# ESP32Weatherstation.net
KiCad netlist of a schematic drawn in EAGLE
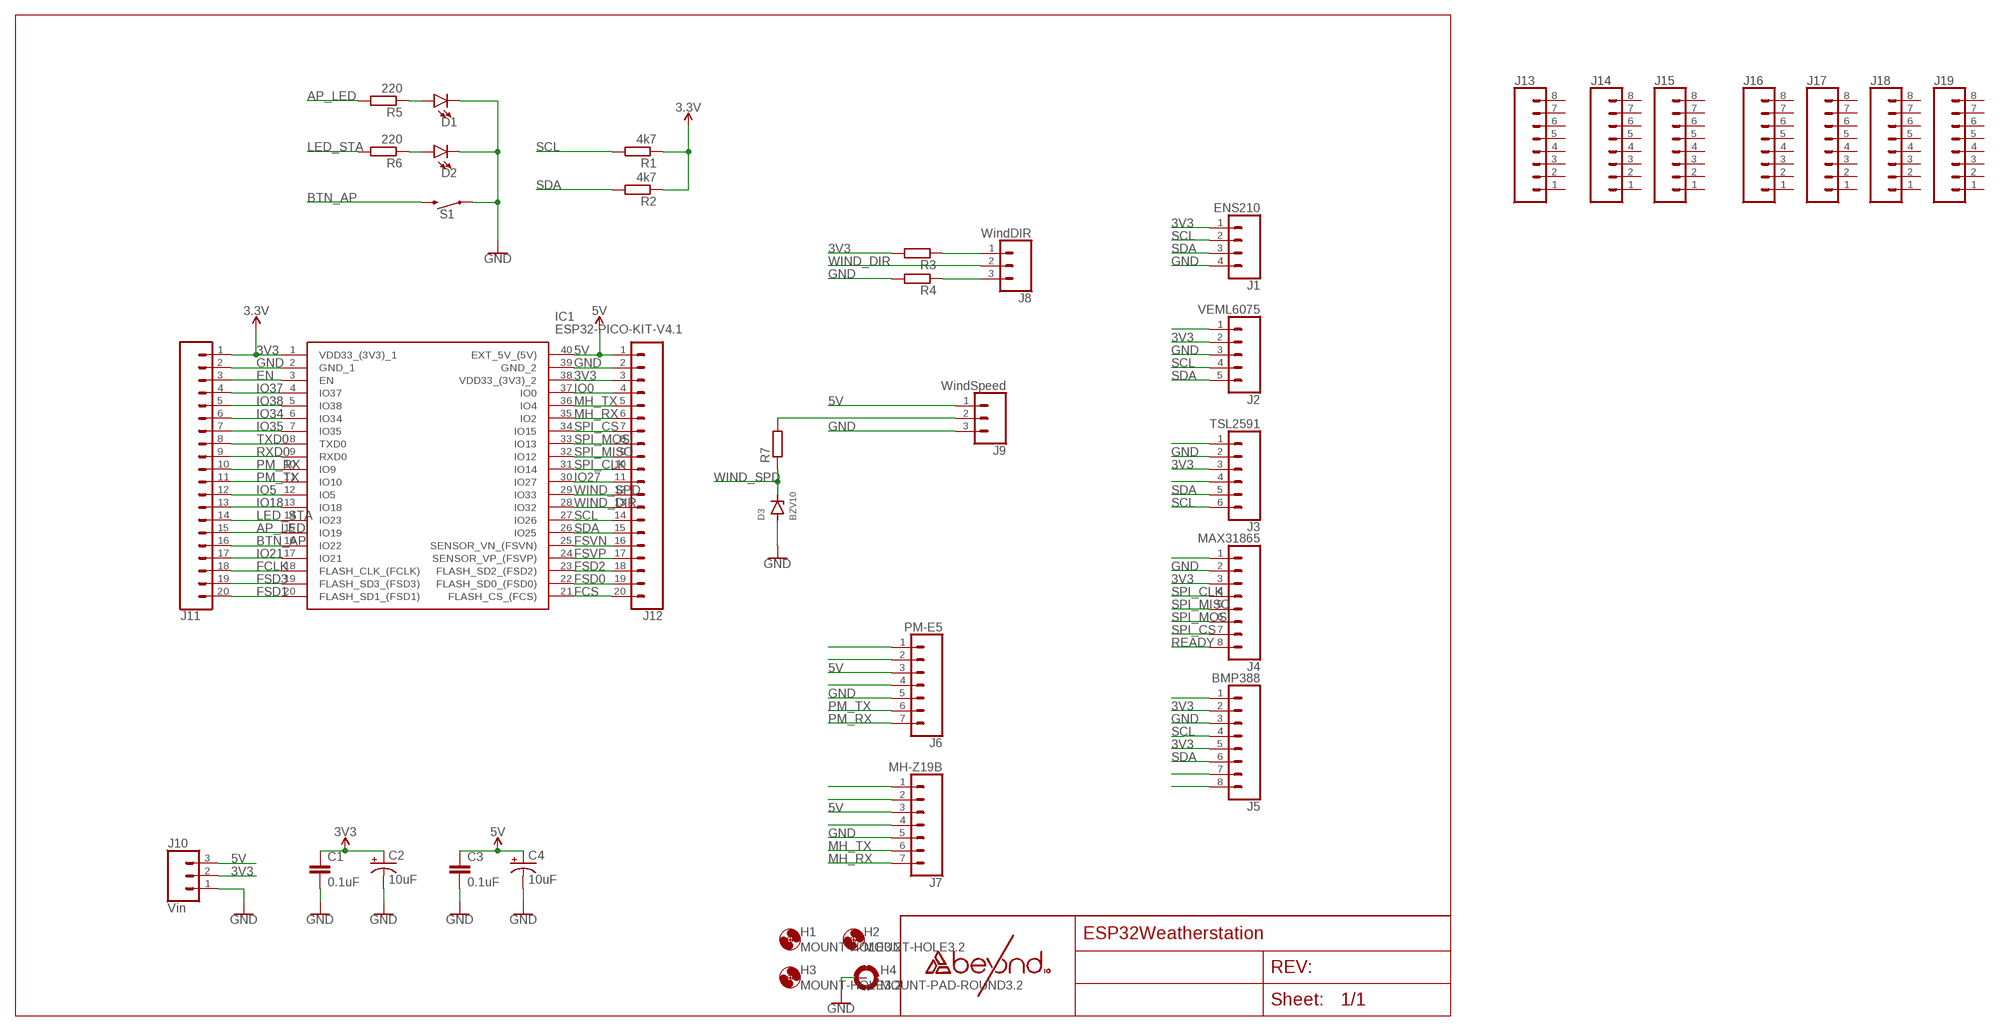
[diagram p0: schematic, sheet 1]

(export (version "E")
  (design (tool "Eeschema 10.0.6"))
  (components
    (comp (ref "C1")
      (value "0.1uF")
      (footprint "eagle-import:0603")
      (libsource (lib "eagle-import") (part "0.1UF-0603-25V-5%"))
    )
    (comp (ref "C2")
      (value "10uF")
      (footprint "eagle-import:EIA3216")
      (libsource (lib "eagle-import") (part "10UF-POLAR-EIA3216-16V-10%(TANT)"))
    )
    (comp (ref "C3")
      (value "0.1uF")
      (footprint "eagle-import:0603")
      (libsource (lib "eagle-import") (part "0.1UF-0603-25V-5%"))
    )
    (comp (ref "C4")
      (value "10uF")
      (footprint "eagle-import:EIA3216")
      (libsource (lib "eagle-import") (part "10UF-POLAR-EIA3216-16V-10%(TANT)"))
    )
    (comp (ref "D1")
      (value "LED3MM")
      (footprint "eagle-import:LED_3MM")
      (libsource (lib "eagle-import") (part "LED3MM"))
    )
    (comp (ref "D2")
      (value "LED3MM")
      (footprint "eagle-import:LED_3MM")
      (libsource (lib "eagle-import") (part "LED3MM"))
    )
    (comp (ref "D3")
      (value "BZV10")
      (footprint "eagle-import:DO34Z7")
      (libsource (lib "eagle-import") (part "BZV10"))
    )
    (comp (ref "H1")
      (value "MOUNT-HOLE3.2")
      (footprint "eagle-import:3,2")
      (libsource (lib "eagle-import") (part "MOUNT-HOLE3.2"))
    )
    (comp (ref "H2")
      (value "MOUNT-HOLE3.2")
      (footprint "eagle-import:3,2")
      (libsource (lib "eagle-import") (part "MOUNT-HOLE3.2"))
    )
    (comp (ref "H3")
      (value "MOUNT-HOLE3.2")
      (footprint "eagle-import:3,2")
      (libsource (lib "eagle-import") (part "MOUNT-HOLE3.2"))
    )
    (comp (ref "H4")
      (value "MOUNT-PAD-ROUND3.2")
      (footprint "eagle-import:3,2-PAD")
      (libsource (lib "eagle-import") (part "MOUNT-PAD-ROUND3.2"))
    )
    (comp (ref "IC1")
      (value "ESP32-PICO-KIT-V4.1")
      (footprint "eagle-import:DIPS1778W60P254L5200H1300Q40N")
      (libsource (lib "eagle-import") (part "ESP32-PICO-KIT-V4.1"))
    )
    (comp (ref "J1")
      (value "ENS210")
      (footprint "eagle-import:1X04_NO_SILK")
      (libsource (lib "eagle-import") (part "CONN_041X04_NO_SILK"))
    )
    (comp (ref "J2")
      (value "VEML6075")
      (footprint "eagle-import:1X05_NO_SILK")
      (libsource (lib "eagle-import") (part "CONN_05NO_SILK"))
    )
    (comp (ref "J3")
      (value "TSL2591")
      (footprint "eagle-import:1X06_NO_SILK")
      (libsource (lib "eagle-import") (part "CONN_06NO_SILK_FEMALE_PTH"))
    )
    (comp (ref "J4")
      (value "MAX31865")
      (footprint "eagle-import:1X08_NO_SILK")
      (libsource (lib "eagle-import") (part "CONN_08NO_SILK_FEMALE_PTH"))
    )
    (comp (ref "J5")
      (value "BMP388")
      (footprint "eagle-import:1X08_NO_SILK")
      (libsource (lib "eagle-import") (part "CONN_08NO_SILK_FEMALE_PTH"))
    )
    (comp (ref "J6")
      (value "PM-E5")
      (footprint "eagle-import:1X07_NO_SILK")
      (libsource (lib "eagle-import") (part "CONN_07NO_SILK"))
    )
    (comp (ref "J7")
      (value "MH-Z19B")
      (footprint "eagle-import:1X07_NO_SILK")
      (libsource (lib "eagle-import") (part "CONN_07NO_SILK"))
    )
    (comp (ref "J8")
      (value "WindDIR")
      (footprint "eagle-import:1X03_NO_SILK")
      (libsource (lib "eagle-import") (part "CONN_031X03_NO_SILK"))
    )
    (comp (ref "J9")
      (value "WindSpeed")
      (footprint "eagle-import:1X03_NO_SILK")
      (libsource (lib "eagle-import") (part "CONN_031X03_NO_SILK"))
    )
    (comp (ref "J10")
      (value "Vin")
      (footprint "eagle-import:1X03_NO_SILK")
      (libsource (lib "eagle-import") (part "CONN_031X03_NO_SILK"))
    )
    (comp (ref "J11")
      (value "CONN_20NOSILK")
      (footprint "eagle-import:1X20_NOSILK")
      (libsource (lib "eagle-import") (part "CONN_20NOSILK"))
    )
    (comp (ref "J12")
      (value "CONN_20NOSILK")
      (footprint "eagle-import:1X20_NOSILK")
      (libsource (lib "eagle-import") (part "CONN_20NOSILK"))
    )
    (comp (ref "J13")
      (value "CONN_08NO_SILK_FEMALE_PTH")
      (footprint "eagle-import:1X08_NO_SILK")
      (libsource (lib "eagle-import") (part "CONN_08NO_SILK_FEMALE_PTH"))
    )
    (comp (ref "J14")
      (value "CONN_08NO_SILK_FEMALE_PTH")
      (footprint "eagle-import:1X08_NO_SILK")
      (libsource (lib "eagle-import") (part "CONN_08NO_SILK_FEMALE_PTH"))
    )
    (comp (ref "J15")
      (value "CONN_08NO_SILK_FEMALE_PTH")
      (footprint "eagle-import:1X08_NO_SILK")
      (libsource (lib "eagle-import") (part "CONN_08NO_SILK_FEMALE_PTH"))
    )
    (comp (ref "J16")
      (value "CONN_08NO_SILK_FEMALE_PTH")
      (footprint "eagle-import:1X08_NO_SILK")
      (libsource (lib "eagle-import") (part "CONN_08NO_SILK_FEMALE_PTH"))
    )
    (comp (ref "J17")
      (value "CONN_08NO_SILK_FEMALE_PTH")
      (footprint "eagle-import:1X08_NO_SILK")
      (libsource (lib "eagle-import") (part "CONN_08NO_SILK_FEMALE_PTH"))
    )
    (comp (ref "J18")
      (value "CONN_08NO_SILK_FEMALE_PTH")
      (footprint "eagle-import:1X08_NO_SILK")
      (libsource (lib "eagle-import") (part "CONN_08NO_SILK_FEMALE_PTH"))
    )
    (comp (ref "J19")
      (value "CONN_08NO_SILK_FEMALE_PTH")
      (footprint "eagle-import:1X08_NO_SILK")
      (libsource (lib "eagle-import") (part "CONN_08NO_SILK_FEMALE_PTH"))
    )
    (comp (ref "R1")
      (value "4k7")
      (footprint "eagle-import:0207_10")
      (libsource (lib "eagle-import") (part "R-EU_0207/10"))
    )
    (comp (ref "R2")
      (value "4k7")
      (footprint "eagle-import:0207_10")
      (libsource (lib "eagle-import") (part "R-EU_0207/10"))
    )
    (comp (ref "R3")
      (value "R-EU_0207/10")
      (footprint "eagle-import:0207_10")
      (libsource (lib "eagle-import") (part "R-EU_0207/10"))
    )
    (comp (ref "R4")
      (value "R-EU_0207/10")
      (footprint "eagle-import:0207_10")
      (libsource (lib "eagle-import") (part "R-EU_0207/10"))
    )
    (comp (ref "R5")
      (value "220")
      (footprint "eagle-import:0207_10")
      (libsource (lib "eagle-import") (part "R-EU_0207/10"))
    )
    (comp (ref "R6")
      (value "220")
      (footprint "eagle-import:0207_10")
      (libsource (lib "eagle-import") (part "R-EU_0207/10"))
    )
    (comp (ref "R7")
      (value "R-EU_0207/10")
      (footprint "eagle-import:0207_10")
      (libsource (lib "eagle-import") (part "R-EU_0207/10"))
    )
    (comp (ref "S1")
      (value "MOMENTARY-SWITCH-SPST-SMD-5.2MM")
      (footprint "eagle-import:TACTILE_SWITCH_SMD_5.2MM")
      (libsource (lib "eagle-import") (part "MOMENTARY-SWITCH-SPST-SMD-5.2MM"))
    )
  )
  (nets
    (net (code "1") (name "/AP_LED") (class "Default")
      (node (ref "IC1") (pin "15") (pinfunction "IO19_15") (pintype "bidirectional"))
      (node (ref "J11") (pin "15") (pinfunction "15_15") (pintype "passive"))
      (node (ref "R5") (pin "2") (pinfunction "2_2") (pintype "passive"))
    )
    (net (code "2") (name "/BTN_AP") (class "Default")
      (node (ref "IC1") (pin "16") (pinfunction "IO22_16") (pintype "bidirectional"))
      (node (ref "J11") (pin "16") (pinfunction "16_16") (pintype "passive"))
      (node (ref "S1") (pin "3") (pinfunction "2_3") (pintype "passive"))
    )
    (net (code "3") (name "/EN") (class "Default")
      (node (ref "IC1") (pin "3") (pinfunction "EN_3") (pintype "input"))
      (node (ref "J11") (pin "3") (pinfunction "3_3") (pintype "passive"))
    )
    (net (code "4") (name "/FCLK") (class "Default")
      (node (ref "IC1") (pin "18") (pinfunction "FLASH_CLK_(FCLK)_18") (pintype "bidirectional"))
      (node (ref "J11") (pin "18") (pinfunction "18_18") (pintype "passive"))
    )
    (net (code "5") (name "/FCS") (class "Default")
      (node (ref "IC1") (pin "21") (pinfunction "FLASH_CS_(FCS)_21") (pintype "bidirectional"))
      (node (ref "J12") (pin "20") (pinfunction "20_20") (pintype "passive"))
    )
    (net (code "6") (name "/FSD0") (class "Default")
      (node (ref "IC1") (pin "22") (pinfunction "FLASH_SD0_(FSD0)_22") (pintype "bidirectional"))
      (node (ref "J12") (pin "19") (pinfunction "19_19") (pintype "passive"))
    )
    (net (code "7") (name "/FSD1") (class "Default")
      (node (ref "IC1") (pin "20") (pinfunction "FLASH_SD1_(FSD1)_20") (pintype "bidirectional"))
      (node (ref "J11") (pin "20") (pinfunction "20_20") (pintype "passive"))
    )
    (net (code "8") (name "/FSD2") (class "Default")
      (node (ref "IC1") (pin "23") (pinfunction "FLASH_SD2_(FSD2)_23") (pintype "bidirectional"))
      (node (ref "J12") (pin "18") (pinfunction "18_18") (pintype "passive"))
    )
    (net (code "9") (name "/FSD3") (class "Default")
      (node (ref "IC1") (pin "19") (pinfunction "FLASH_SD3_(FSD3)_19") (pintype "bidirectional"))
      (node (ref "J11") (pin "19") (pinfunction "19_19") (pintype "passive"))
    )
    (net (code "10") (name "/FSVN") (class "Default")
      (node (ref "IC1") (pin "25") (pinfunction "SENSOR_VN_(FSVN)_25") (pintype "input"))
      (node (ref "J12") (pin "16") (pinfunction "16_16") (pintype "passive"))
    )
    (net (code "11") (name "/FSVP") (class "Default")
      (node (ref "IC1") (pin "24") (pinfunction "SENSOR_VP_(FSVP)_24") (pintype "input"))
      (node (ref "J12") (pin "17") (pinfunction "17_17") (pintype "passive"))
    )
    (net (code "12") (name "/IO0") (class "Default")
      (node (ref "IC1") (pin "37") (pinfunction "IO0_37") (pintype "bidirectional"))
      (node (ref "J12") (pin "4") (pinfunction "4_4") (pintype "passive"))
    )
    (net (code "13") (name "/IO5") (class "Default")
      (node (ref "IC1") (pin "12") (pinfunction "IO5_12") (pintype "bidirectional"))
      (node (ref "J11") (pin "12") (pinfunction "12_12") (pintype "passive"))
    )
    (net (code "14") (name "/IO18") (class "Default")
      (node (ref "IC1") (pin "13") (pinfunction "IO18_13") (pintype "bidirectional"))
      (node (ref "J11") (pin "13") (pinfunction "13_13") (pintype "passive"))
    )
    (net (code "15") (name "/IO21") (class "Default")
      (node (ref "IC1") (pin "17") (pinfunction "IO21_17") (pintype "bidirectional"))
      (node (ref "J11") (pin "17") (pinfunction "17_17") (pintype "passive"))
    )
    (net (code "16") (name "/IO27") (class "Default")
      (node (ref "IC1") (pin "30") (pinfunction "IO27_30") (pintype "bidirectional"))
      (node (ref "J12") (pin "11") (pinfunction "11_11") (pintype "passive"))
    )
    (net (code "17") (name "/IO34") (class "Default")
      (node (ref "IC1") (pin "6") (pinfunction "IO34_6") (pintype "input"))
      (node (ref "J11") (pin "6") (pinfunction "6_6") (pintype "passive"))
    )
    (net (code "18") (name "/IO35") (class "Default")
      (node (ref "IC1") (pin "7") (pinfunction "IO35_7") (pintype "input"))
      (node (ref "J11") (pin "7") (pinfunction "7_7") (pintype "passive"))
    )
    (net (code "19") (name "/IO37") (class "Default")
      (node (ref "IC1") (pin "4") (pinfunction "IO37_4") (pintype "input"))
      (node (ref "J11") (pin "4") (pinfunction "4_4") (pintype "passive"))
    )
    (net (code "20") (name "/IO38") (class "Default")
      (node (ref "IC1") (pin "5") (pinfunction "IO38_5") (pintype "input"))
      (node (ref "J11") (pin "5") (pinfunction "5_5") (pintype "passive"))
    )
    (net (code "21") (name "/LED_STA") (class "Default")
      (node (ref "IC1") (pin "14") (pinfunction "IO23_14") (pintype "bidirectional"))
      (node (ref "J11") (pin "14") (pinfunction "14_14") (pintype "passive"))
      (node (ref "R6") (pin "2") (pinfunction "2_2") (pintype "passive"))
    )
    (net (code "22") (name "/MH_RX") (class "Default")
      (node (ref "IC1") (pin "35") (pinfunction "IO2_35") (pintype "bidirectional"))
      (node (ref "J12") (pin "6") (pinfunction "6_6") (pintype "passive"))
      (node (ref "J7") (pin "7") (pinfunction "7_7") (pintype "passive"))
    )
    (net (code "23") (name "/MH_TX") (class "Default")
      (node (ref "IC1") (pin "36") (pinfunction "IO4_36") (pintype "bidirectional"))
      (node (ref "J12") (pin "5") (pinfunction "5_5") (pintype "passive"))
      (node (ref "J7") (pin "6") (pinfunction "6_6") (pintype "passive"))
    )
    (net (code "24") (name "/PM_RX") (class "Default")
      (node (ref "IC1") (pin "10") (pinfunction "IO9_10") (pintype "bidirectional"))
      (node (ref "J11") (pin "10") (pinfunction "10_10") (pintype "passive"))
      (node (ref "J6") (pin "7") (pinfunction "7_7") (pintype "passive"))
    )
    (net (code "25") (name "/PM_TX") (class "Default")
      (node (ref "IC1") (pin "11") (pinfunction "IO10_11") (pintype "bidirectional"))
      (node (ref "J11") (pin "11") (pinfunction "11_11") (pintype "passive"))
      (node (ref "J6") (pin "6") (pinfunction "6_6") (pintype "passive"))
    )
    (net (code "26") (name "/READY") (class "Default")
      (node (ref "J4") (pin "8") (pinfunction "8_8") (pintype "passive"))
    )
    (net (code "27") (name "/RXD0") (class "Default")
      (node (ref "IC1") (pin "9") (pinfunction "RXD0_9") (pintype "bidirectional"))
      (node (ref "J11") (pin "9") (pinfunction "9_9") (pintype "passive"))
    )
    (net (code "28") (name "/SCL") (class "Default")
      (node (ref "IC1") (pin "27") (pinfunction "IO26_27") (pintype "bidirectional"))
      (node (ref "J1") (pin "2") (pinfunction "2_2") (pintype "passive"))
      (node (ref "J12") (pin "14") (pinfunction "14_14") (pintype "passive"))
      (node (ref "J2") (pin "4") (pinfunction "4_4") (pintype "passive"))
      (node (ref "J3") (pin "6") (pinfunction "6_6") (pintype "passive"))
      (node (ref "J5") (pin "4") (pinfunction "4_4") (pintype "passive"))
      (node (ref "R1") (pin "2") (pinfunction "2_2") (pintype "passive"))
    )
    (net (code "29") (name "/SDA") (class "Default")
      (node (ref "IC1") (pin "26") (pinfunction "IO25_26") (pintype "bidirectional"))
      (node (ref "J1") (pin "3") (pinfunction "3_3") (pintype "passive"))
      (node (ref "J12") (pin "15") (pinfunction "15_15") (pintype "passive"))
      (node (ref "J2") (pin "5") (pinfunction "5_5") (pintype "passive"))
      (node (ref "J3") (pin "5") (pinfunction "5_5") (pintype "passive"))
      (node (ref "J5") (pin "6") (pinfunction "6_6") (pintype "passive"))
      (node (ref "R2") (pin "2") (pinfunction "2_2") (pintype "passive"))
    )
    (net (code "30") (name "/SPI_CLK") (class "Default")
      (node (ref "IC1") (pin "31") (pinfunction "IO14_31") (pintype "bidirectional"))
      (node (ref "J12") (pin "10") (pinfunction "10_10") (pintype "passive"))
      (node (ref "J4") (pin "4") (pinfunction "4_4") (pintype "passive"))
    )
    (net (code "31") (name "/SPI_CS") (class "Default")
      (node (ref "IC1") (pin "34") (pinfunction "IO15_34") (pintype "bidirectional"))
      (node (ref "J12") (pin "7") (pinfunction "7_7") (pintype "passive"))
      (node (ref "J4") (pin "7") (pinfunction "7_7") (pintype "passive"))
    )
    (net (code "32") (name "/SPI_MISO") (class "Default")
      (node (ref "IC1") (pin "32") (pinfunction "IO12_32") (pintype "bidirectional"))
      (node (ref "J12") (pin "9") (pinfunction "9_9") (pintype "passive"))
      (node (ref "J4") (pin "5") (pinfunction "5_5") (pintype "passive"))
    )
    (net (code "33") (name "/SPI_MOSI") (class "Default")
      (node (ref "IC1") (pin "33") (pinfunction "IO13_33") (pintype "bidirectional"))
      (node (ref "J12") (pin "8") (pinfunction "8_8") (pintype "passive"))
      (node (ref "J4") (pin "6") (pinfunction "6_6") (pintype "passive"))
    )
    (net (code "34") (name "/TXD0") (class "Default")
      (node (ref "IC1") (pin "8") (pinfunction "TXD0_8") (pintype "bidirectional"))
      (node (ref "J11") (pin "8") (pinfunction "8_8") (pintype "passive"))
    )
    (net (code "35") (name "/WIND_DIR") (class "Default")
      (node (ref "IC1") (pin "28") (pinfunction "IO32_28") (pintype "bidirectional"))
      (node (ref "J12") (pin "13") (pinfunction "13_13") (pintype "passive"))
      (node (ref "J8") (pin "2") (pinfunction "2_2") (pintype "passive"))
    )
    (net (code "36") (name "/WIND_SPD") (class "Default")
      (node (ref "D3") (pin "C") (pinfunction "C_C") (pintype "passive"))
      (node (ref "IC1") (pin "29") (pinfunction "IO33_29") (pintype "bidirectional"))
      (node (ref "J12") (pin "12") (pinfunction "12_12") (pintype "passive"))
      (node (ref "R7") (pin "1") (pinfunction "1_1") (pintype "passive"))
    )
    (net (code "37") (name "3.3V") (class "Default")
      (node (ref "C1") (pin "1") (pinfunction "1_1") (pintype "passive"))
      (node (ref "C2") (pin "+") (pinfunction "+_+") (pintype "passive"))
      (node (ref "IC1") (pin "1") (pinfunction "VDD33_(3V3)_1_1") (pintype "power_in"))
      (node (ref "IC1") (pin "38") (pinfunction "VDD33_(3V3)_2_38") (pintype "power_in"))
      (node (ref "J1") (pin "1") (pinfunction "1_1") (pintype "passive"))
      (node (ref "J10") (pin "2") (pinfunction "2_2") (pintype "passive"))
      (node (ref "J11") (pin "1") (pinfunction "1_1") (pintype "passive"))
      (node (ref "J12") (pin "3") (pinfunction "3_3") (pintype "passive"))
      (node (ref "J2") (pin "2") (pinfunction "2_2") (pintype "passive"))
      (node (ref "J3") (pin "3") (pinfunction "3_3") (pintype "passive"))
      (node (ref "J4") (pin "3") (pinfunction "3_3") (pintype "passive"))
      (node (ref "J5") (pin "2") (pinfunction "2_2") (pintype "passive"))
      (node (ref "J5") (pin "5") (pinfunction "5_5") (pintype "passive"))
      (node (ref "R1") (pin "1") (pinfunction "1_1") (pintype "passive"))
      (node (ref "R2") (pin "1") (pinfunction "1_1") (pintype "passive"))
      (node (ref "R3") (pin "2") (pinfunction "2_2") (pintype "passive"))
    )
    (net (code "38") (name "5V") (class "Default")
      (node (ref "C3") (pin "1") (pinfunction "1_1") (pintype "passive"))
      (node (ref "C4") (pin "+") (pinfunction "+_+") (pintype "passive"))
      (node (ref "IC1") (pin "40") (pinfunction "EXT_5V_(5V)_40") (pintype "power_in"))
      (node (ref "J10") (pin "3") (pinfunction "3_3") (pintype "passive"))
      (node (ref "J12") (pin "1") (pinfunction "1_1") (pintype "passive"))
      (node (ref "J6") (pin "3") (pinfunction "3_3") (pintype "passive"))
      (node (ref "J7") (pin "3") (pinfunction "3_3") (pintype "passive"))
      (node (ref "J9") (pin "1") (pinfunction "1_1") (pintype "passive"))
    )
    (net (code "39") (name "GND") (class "Default")
      (node (ref "C1") (pin "2") (pinfunction "2_2") (pintype "passive"))
      (node (ref "C2") (pin "-") (pinfunction "-_-") (pintype "passive"))
      (node (ref "C3") (pin "2") (pinfunction "2_2") (pintype "passive"))
      (node (ref "C4") (pin "-") (pinfunction "-_-") (pintype "passive"))
      (node (ref "D1") (pin "K") (pinfunction "C_K") (pintype "passive"))
      (node (ref "D2") (pin "K") (pinfunction "C_K") (pintype "passive"))
      (node (ref "D3") (pin "A") (pinfunction "A_A") (pintype "passive"))
      (node (ref "H4") (pin "B3,2") (pinfunction "MOUNT_B3,2") (pintype "passive"))
      (node (ref "IC1") (pin "2") (pinfunction "GND_1_2") (pintype "power_in"))
      (node (ref "IC1") (pin "39") (pinfunction "GND_2_39") (pintype "power_in"))
      (node (ref "J1") (pin "4") (pinfunction "4_4") (pintype "passive"))
      (node (ref "J10") (pin "1") (pinfunction "1_1") (pintype "passive"))
      (node (ref "J11") (pin "2") (pinfunction "2_2") (pintype "passive"))
      (node (ref "J12") (pin "2") (pinfunction "2_2") (pintype "passive"))
      (node (ref "J2") (pin "3") (pinfunction "3_3") (pintype "passive"))
      (node (ref "J3") (pin "2") (pinfunction "2_2") (pintype "passive"))
      (node (ref "J4") (pin "2") (pinfunction "2_2") (pintype "passive"))
      (node (ref "J5") (pin "3") (pinfunction "3_3") (pintype "passive"))
      (node (ref "J6") (pin "5") (pinfunction "5_5") (pintype "passive"))
      (node (ref "J7") (pin "5") (pinfunction "5_5") (pintype "passive"))
      (node (ref "J9") (pin "3") (pinfunction "3_3") (pintype "passive"))
      (node (ref "R4") (pin "2") (pinfunction "2_2") (pintype "passive"))
      (node (ref "S1") (pin "1") (pinfunction "1_1") (pintype "passive"))
    )
    (net (code "40") (name "Net-(D1-PadA)") (class "Default")
      (node (ref "D1") (pin "A") (pinfunction "A_A") (pintype "passive"))
      (node (ref "R5") (pin "1") (pinfunction "1_1") (pintype "passive"))
    )
    (net (code "41") (name "Net-(D2-PadA)") (class "Default")
      (node (ref "D2") (pin "A") (pinfunction "A_A") (pintype "passive"))
      (node (ref "R6") (pin "1") (pinfunction "1_1") (pintype "passive"))
    )
    (net (code "42") (name "Net-(J8-Pad1)") (class "Default")
      (node (ref "J8") (pin "1") (pinfunction "1_1") (pintype "passive"))
      (node (ref "R3") (pin "1") (pinfunction "1_1") (pintype "passive"))
    )
    (net (code "43") (name "Net-(J8-Pad3)") (class "Default")
      (node (ref "J8") (pin "3") (pinfunction "3_3") (pintype "passive"))
      (node (ref "R4") (pin "1") (pinfunction "1_1") (pintype "passive"))
    )
    (net (code "44") (name "Net-(J9-Pad2)") (class "Default")
      (node (ref "J9") (pin "2") (pinfunction "2_2") (pintype "passive"))
      (node (ref "R7") (pin "2") (pinfunction "2_2") (pintype "passive"))
    )
    (net (code "45") (name "unconnected-(J2-Pad1)") (class "Default")
      (node (ref "J2") (pin "1") (pinfunction "1_1") (pintype "passive"))
    )
    (net (code "46") (name "unconnected-(J3-Pad1)") (class "Default")
      (node (ref "J3") (pin "1") (pinfunction "1_1") (pintype "passive"))
    )
    (net (code "47") (name "unconnected-(J3-Pad4)") (class "Default")
      (node (ref "J3") (pin "4") (pinfunction "4_4") (pintype "passive"))
    )
    (net (code "48") (name "unconnected-(J4-Pad1)") (class "Default")
      (node (ref "J4") (pin "1") (pinfunction "1_1") (pintype "passive"))
    )
    (net (code "49") (name "unconnected-(J5-Pad1)") (class "Default")
      (node (ref "J5") (pin "1") (pinfunction "1_1") (pintype "passive"))
    )
    (net (code "50") (name "unconnected-(J5-Pad7)") (class "Default")
      (node (ref "J5") (pin "7") (pinfunction "7_7") (pintype "passive"))
    )
    (net (code "51") (name "unconnected-(J5-Pad8)") (class "Default")
      (node (ref "J5") (pin "8") (pinfunction "8_8") (pintype "passive"))
    )
    (net (code "52") (name "unconnected-(J6-Pad1)") (class "Default")
      (node (ref "J6") (pin "1") (pinfunction "1_1") (pintype "passive"))
    )
    (net (code "53") (name "unconnected-(J6-Pad2)") (class "Default")
      (node (ref "J6") (pin "2") (pinfunction "2_2") (pintype "passive"))
    )
    (net (code "54") (name "unconnected-(J6-Pad4)") (class "Default")
      (node (ref "J6") (pin "4") (pinfunction "4_4") (pintype "passive"))
    )
    (net (code "55") (name "unconnected-(J7-Pad1)") (class "Default")
      (node (ref "J7") (pin "1") (pinfunction "1_1") (pintype "passive"))
    )
    (net (code "56") (name "unconnected-(J7-Pad2)") (class "Default")
      (node (ref "J7") (pin "2") (pinfunction "2_2") (pintype "passive"))
    )
    (net (code "57") (name "unconnected-(J7-Pad4)") (class "Default")
      (node (ref "J7") (pin "4") (pinfunction "4_4") (pintype "passive"))
    )
    (net (code "58") (name "unconnected-(J13-Pad1)") (class "Default")
      (node (ref "J13") (pin "1") (pinfunction "1_1") (pintype "passive"))
    )
    (net (code "59") (name "unconnected-(J13-Pad2)") (class "Default")
      (node (ref "J13") (pin "2") (pinfunction "2_2") (pintype "passive"))
    )
    (net (code "60") (name "unconnected-(J13-Pad3)") (class "Default")
      (node (ref "J13") (pin "3") (pinfunction "3_3") (pintype "passive"))
    )
    (net (code "61") (name "unconnected-(J13-Pad4)") (class "Default")
      (node (ref "J13") (pin "4") (pinfunction "4_4") (pintype "passive"))
    )
    (net (code "62") (name "unconnected-(J13-Pad5)") (class "Default")
      (node (ref "J13") (pin "5") (pinfunction "5_5") (pintype "passive"))
    )
    (net (code "63") (name "unconnected-(J13-Pad6)") (class "Default")
      (node (ref "J13") (pin "6") (pinfunction "6_6") (pintype "passive"))
    )
    (net (code "64") (name "unconnected-(J13-Pad7)") (class "Default")
      (node (ref "J13") (pin "7") (pinfunction "7_7") (pintype "passive"))
    )
    (net (code "65") (name "unconnected-(J13-Pad8)") (class "Default")
      (node (ref "J13") (pin "8") (pinfunction "8_8") (pintype "passive"))
    )
    (net (code "66") (name "unconnected-(J14-Pad1)") (class "Default")
      (node (ref "J14") (pin "1") (pinfunction "1_1") (pintype "passive"))
    )
    (net (code "67") (name "unconnected-(J14-Pad2)") (class "Default")
      (node (ref "J14") (pin "2") (pinfunction "2_2") (pintype "passive"))
    )
    (net (code "68") (name "unconnected-(J14-Pad3)") (class "Default")
      (node (ref "J14") (pin "3") (pinfunction "3_3") (pintype "passive"))
    )
    (net (code "69") (name "unconnected-(J14-Pad4)") (class "Default")
      (node (ref "J14") (pin "4") (pinfunction "4_4") (pintype "passive"))
    )
    (net (code "70") (name "unconnected-(J14-Pad5)") (class "Default")
      (node (ref "J14") (pin "5") (pinfunction "5_5") (pintype "passive"))
    )
    (net (code "71") (name "unconnected-(J14-Pad6)") (class "Default")
      (node (ref "J14") (pin "6") (pinfunction "6_6") (pintype "passive"))
    )
    (net (code "72") (name "unconnected-(J14-Pad7)") (class "Default")
      (node (ref "J14") (pin "7") (pinfunction "7_7") (pintype "passive"))
    )
    (net (code "73") (name "unconnected-(J14-Pad8)") (class "Default")
      (node (ref "J14") (pin "8") (pinfunction "8_8") (pintype "passive"))
    )
    (net (code "74") (name "unconnected-(J15-Pad1)") (class "Default")
      (node (ref "J15") (pin "1") (pinfunction "1_1") (pintype "passive"))
    )
    (net (code "75") (name "unconnected-(J15-Pad2)") (class "Default")
      (node (ref "J15") (pin "2") (pinfunction "2_2") (pintype "passive"))
    )
    (net (code "76") (name "unconnected-(J15-Pad3)") (class "Default")
      (node (ref "J15") (pin "3") (pinfunction "3_3") (pintype "passive"))
    )
    (net (code "77") (name "unconnected-(J15-Pad4)") (class "Default")
      (node (ref "J15") (pin "4") (pinfunction "4_4") (pintype "passive"))
    )
    (net (code "78") (name "unconnected-(J15-Pad5)") (class "Default")
      (node (ref "J15") (pin "5") (pinfunction "5_5") (pintype "passive"))
    )
    (net (code "79") (name "unconnected-(J15-Pad6)") (class "Default")
      (node (ref "J15") (pin "6") (pinfunction "6_6") (pintype "passive"))
    )
    (net (code "80") (name "unconnected-(J15-Pad7)") (class "Default")
      (node (ref "J15") (pin "7") (pinfunction "7_7") (pintype "passive"))
    )
    (net (code "81") (name "unconnected-(J15-Pad8)") (class "Default")
      (node (ref "J15") (pin "8") (pinfunction "8_8") (pintype "passive"))
    )
    (net (code "82") (name "unconnected-(J16-Pad1)") (class "Default")
      (node (ref "J16") (pin "1") (pinfunction "1_1") (pintype "passive"))
    )
    (net (code "83") (name "unconnected-(J16-Pad2)") (class "Default")
      (node (ref "J16") (pin "2") (pinfunction "2_2") (pintype "passive"))
    )
    (net (code "84") (name "unconnected-(J16-Pad3)") (class "Default")
      (node (ref "J16") (pin "3") (pinfunction "3_3") (pintype "passive"))
    )
    (net (code "85") (name "unconnected-(J16-Pad4)") (class "Default")
      (node (ref "J16") (pin "4") (pinfunction "4_4") (pintype "passive"))
    )
    (net (code "86") (name "unconnected-(J16-Pad5)") (class "Default")
      (node (ref "J16") (pin "5") (pinfunction "5_5") (pintype "passive"))
    )
    (net (code "87") (name "unconnected-(J16-Pad6)") (class "Default")
      (node (ref "J16") (pin "6") (pinfunction "6_6") (pintype "passive"))
    )
    (net (code "88") (name "unconnected-(J16-Pad7)") (class "Default")
      (node (ref "J16") (pin "7") (pinfunction "7_7") (pintype "passive"))
    )
    (net (code "89") (name "unconnected-(J16-Pad8)") (class "Default")
      (node (ref "J16") (pin "8") (pinfunction "8_8") (pintype "passive"))
    )
    (net (code "90") (name "unconnected-(J17-Pad1)") (class "Default")
      (node (ref "J17") (pin "1") (pinfunction "1_1") (pintype "passive"))
    )
    (net (code "91") (name "unconnected-(J17-Pad2)") (class "Default")
      (node (ref "J17") (pin "2") (pinfunction "2_2") (pintype "passive"))
    )
    (net (code "92") (name "unconnected-(J17-Pad3)") (class "Default")
      (node (ref "J17") (pin "3") (pinfunction "3_3") (pintype "passive"))
    )
    (net (code "93") (name "unconnected-(J17-Pad4)") (class "Default")
      (node (ref "J17") (pin "4") (pinfunction "4_4") (pintype "passive"))
    )
    (net (code "94") (name "unconnected-(J17-Pad5)") (class "Default")
      (node (ref "J17") (pin "5") (pinfunction "5_5") (pintype "passive"))
    )
    (net (code "95") (name "unconnected-(J17-Pad6)") (class "Default")
      (node (ref "J17") (pin "6") (pinfunction "6_6") (pintype "passive"))
    )
    (net (code "96") (name "unconnected-(J17-Pad7)") (class "Default")
      (node (ref "J17") (pin "7") (pinfunction "7_7") (pintype "passive"))
    )
    (net (code "97") (name "unconnected-(J17-Pad8)") (class "Default")
      (node (ref "J17") (pin "8") (pinfunction "8_8") (pintype "passive"))
    )
    (net (code "98") (name "unconnected-(J18-Pad1)") (class "Default")
      (node (ref "J18") (pin "1") (pinfunction "1_1") (pintype "passive"))
    )
    (net (code "99") (name "unconnected-(J18-Pad2)") (class "Default")
      (node (ref "J18") (pin "2") (pinfunction "2_2") (pintype "passive"))
    )
    (net (code "100") (name "unconnected-(J18-Pad3)") (class "Default")
      (node (ref "J18") (pin "3") (pinfunction "3_3") (pintype "passive"))
    )
    (net (code "101") (name "unconnected-(J18-Pad4)") (class "Default")
      (node (ref "J18") (pin "4") (pinfunction "4_4") (pintype "passive"))
    )
    (net (code "102") (name "unconnected-(J18-Pad5)") (class "Default")
      (node (ref "J18") (pin "5") (pinfunction "5_5") (pintype "passive"))
    )
    (net (code "103") (name "unconnected-(J18-Pad6)") (class "Default")
      (node (ref "J18") (pin "6") (pinfunction "6_6") (pintype "passive"))
    )
    (net (code "104") (name "unconnected-(J18-Pad7)") (class "Default")
      (node (ref "J18") (pin "7") (pinfunction "7_7") (pintype "passive"))
    )
    (net (code "105") (name "unconnected-(J18-Pad8)") (class "Default")
      (node (ref "J18") (pin "8") (pinfunction "8_8") (pintype "passive"))
    )
    (net (code "106") (name "unconnected-(J19-Pad1)") (class "Default")
      (node (ref "J19") (pin "1") (pinfunction "1_1") (pintype "passive"))
    )
    (net (code "107") (name "unconnected-(J19-Pad2)") (class "Default")
      (node (ref "J19") (pin "2") (pinfunction "2_2") (pintype "passive"))
    )
    (net (code "108") (name "unconnected-(J19-Pad3)") (class "Default")
      (node (ref "J19") (pin "3") (pinfunction "3_3") (pintype "passive"))
    )
    (net (code "109") (name "unconnected-(J19-Pad4)") (class "Default")
      (node (ref "J19") (pin "4") (pinfunction "4_4") (pintype "passive"))
    )
    (net (code "110") (name "unconnected-(J19-Pad5)") (class "Default")
      (node (ref "J19") (pin "5") (pinfunction "5_5") (pintype "passive"))
    )
    (net (code "111") (name "unconnected-(J19-Pad6)") (class "Default")
      (node (ref "J19") (pin "6") (pinfunction "6_6") (pintype "passive"))
    )
    (net (code "112") (name "unconnected-(J19-Pad7)") (class "Default")
      (node (ref "J19") (pin "7") (pinfunction "7_7") (pintype "passive"))
    )
    (net (code "113") (name "unconnected-(J19-Pad8)") (class "Default")
      (node (ref "J19") (pin "8") (pinfunction "8_8") (pintype "passive"))
    )
  )
)
